# Mainboard.net
KiCad netlist of a schematic drawn in EAGLE
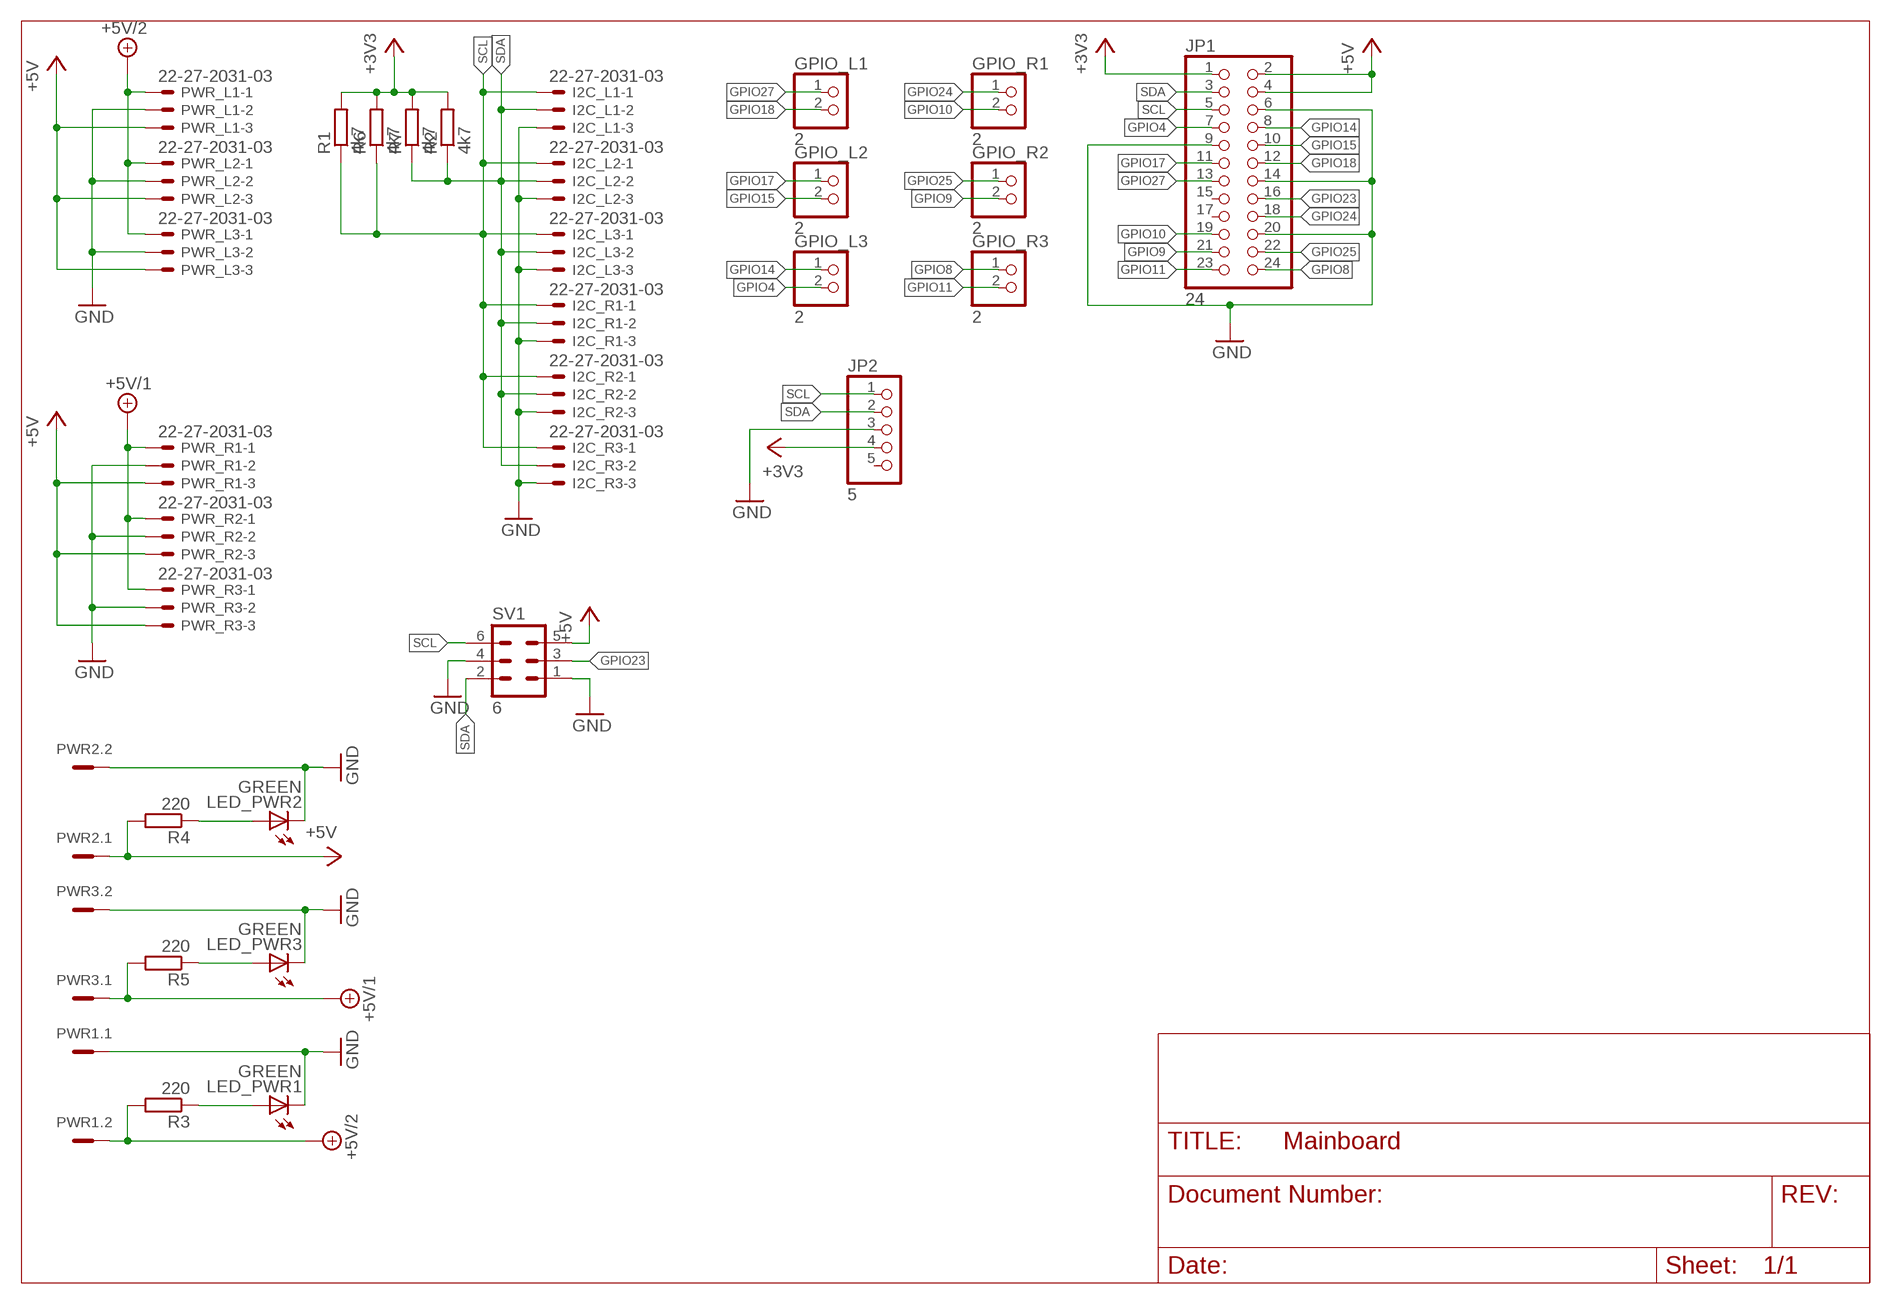
[diagram p0: schematic, sheet 1]

(export (version "E")
  (design (tool "Eeschema 10.0.6"))
  (components
    (comp (ref "GPIO_L1")
      (value "2")
      (footprint "eagle-import:1X02")
      (libsource (lib "eagle-import") (part "PINHD-1X2"))
    )
    (comp (ref "GPIO_L2")
      (value "2")
      (footprint "eagle-import:1X02")
      (libsource (lib "eagle-import") (part "PINHD-1X2"))
    )
    (comp (ref "GPIO_L3")
      (value "2")
      (footprint "eagle-import:1X02")
      (libsource (lib "eagle-import") (part "PINHD-1X2"))
    )
    (comp (ref "GPIO_R1")
      (value "2")
      (footprint "eagle-import:1X02")
      (libsource (lib "eagle-import") (part "PINHD-1X2"))
    )
    (comp (ref "GPIO_R2")
      (value "2")
      (footprint "eagle-import:1X02")
      (libsource (lib "eagle-import") (part "PINHD-1X2"))
    )
    (comp (ref "GPIO_R3")
      (value "2")
      (footprint "eagle-import:1X02")
      (libsource (lib "eagle-import") (part "PINHD-1X2"))
    )
    (comp (ref "I2C_L1")
      (value "22-27-2031-03")
      (footprint "eagle-import:6410-03")
      (libsource (lib "eagle-import") (part "22-?-0327-2031"))
    )
    (comp (ref "I2C_L2")
      (value "22-27-2031-03")
      (footprint "eagle-import:6410-03")
      (libsource (lib "eagle-import") (part "22-?-0327-2031"))
    )
    (comp (ref "I2C_L3")
      (value "22-27-2031-03")
      (footprint "eagle-import:6410-03")
      (libsource (lib "eagle-import") (part "22-?-0327-2031"))
    )
    (comp (ref "I2C_R1")
      (value "22-27-2031-03")
      (footprint "eagle-import:6410-03")
      (libsource (lib "eagle-import") (part "22-?-0327-2031"))
    )
    (comp (ref "I2C_R2")
      (value "22-27-2031-03")
      (footprint "eagle-import:6410-03")
      (libsource (lib "eagle-import") (part "22-?-0327-2031"))
    )
    (comp (ref "I2C_R3")
      (value "22-27-2031-03")
      (footprint "eagle-import:6410-03")
      (libsource (lib "eagle-import") (part "22-?-0327-2031"))
    )
    (comp (ref "JP1")
      (value "24")
      (footprint "eagle-import:2X12")
      (libsource (lib "eagle-import") (part "PINHD-2X12"))
    )
    (comp (ref "JP2")
      (value "5")
      (footprint "eagle-import:1X05")
      (libsource (lib "eagle-import") (part "PINHD-1X5"))
    )
    (comp (ref "LED_PWR1")
      (value "GREEN")
      (footprint "eagle-import:CHIP-LED0805")
      (libsource (lib "eagle-import") (part "LEDCHIP-LED0805"))
    )
    (comp (ref "LED_PWR2")
      (value "GREEN")
      (footprint "eagle-import:CHIP-LED0805")
      (libsource (lib "eagle-import") (part "LEDCHIP-LED0805"))
    )
    (comp (ref "LED_PWR3")
      (value "GREEN")
      (footprint "eagle-import:CHIP-LED0805")
      (libsource (lib "eagle-import") (part "LEDCHIP-LED0805"))
    )
    (comp (ref "PWR1")
      (value "MCV2")
      (footprint "eagle-import:MCV2")
      (libsource (lib "eagle-import") (part "MCV2"))
    )
    (comp (ref "PWR2")
      (value "MCV2")
      (footprint "eagle-import:MCV2")
      (libsource (lib "eagle-import") (part "MCV2"))
    )
    (comp (ref "PWR3")
      (value "MCV2")
      (footprint "eagle-import:MCV2")
      (libsource (lib "eagle-import") (part "MCV2"))
    )
    (comp (ref "PWR_L1")
      (value "22-27-2031-03")
      (footprint "eagle-import:6410-03")
      (libsource (lib "eagle-import") (part "22-?-0327-2031"))
    )
    (comp (ref "PWR_L2")
      (value "22-27-2031-03")
      (footprint "eagle-import:6410-03")
      (libsource (lib "eagle-import") (part "22-?-0327-2031"))
    )
    (comp (ref "PWR_L3")
      (value "22-27-2031-03")
      (footprint "eagle-import:6410-03")
      (libsource (lib "eagle-import") (part "22-?-0327-2031"))
    )
    (comp (ref "PWR_R1")
      (value "22-27-2031-03")
      (footprint "eagle-import:6410-03")
      (libsource (lib "eagle-import") (part "22-?-0327-2031"))
    )
    (comp (ref "PWR_R2")
      (value "22-27-2031-03")
      (footprint "eagle-import:6410-03")
      (libsource (lib "eagle-import") (part "22-?-0327-2031"))
    )
    (comp (ref "PWR_R3")
      (value "22-27-2031-03")
      (footprint "eagle-import:6410-03")
      (libsource (lib "eagle-import") (part "22-?-0327-2031"))
    )
    (comp (ref "R1")
      (value "4k7")
      (footprint "eagle-import:R0805")
      (libsource (lib "eagle-import") (part "R-EU_R0805"))
    )
    (comp (ref "R2")
      (value "4k7")
      (footprint "eagle-import:R0805")
      (libsource (lib "eagle-import") (part "R-EU_R0805"))
    )
    (comp (ref "R3")
      (value "220")
      (footprint "eagle-import:R0805")
      (libsource (lib "eagle-import") (part "R-EU_R0805"))
    )
    (comp (ref "R4")
      (value "220")
      (footprint "eagle-import:R0805")
      (libsource (lib "eagle-import") (part "R-EU_R0805"))
    )
    (comp (ref "R5")
      (value "220")
      (footprint "eagle-import:R0805")
      (libsource (lib "eagle-import") (part "R-EU_R0805"))
    )
    (comp (ref "R6")
      (value "4k7")
      (footprint "eagle-import:R0805")
      (libsource (lib "eagle-import") (part "R-EU_R0805"))
    )
    (comp (ref "R7")
      (value "4k7")
      (footprint "eagle-import:R0805")
      (libsource (lib "eagle-import") (part "R-EU_R0805"))
    )
    (comp (ref "SV1")
      (value "6")
      (footprint "eagle-import:ML6")
      (libsource (lib "eagle-import") (part "ML6"))
    )
  )
  (nets
    (net (code "1") (name "+3V3") (class "Default")
      (node (ref "JP1") (pin "1") (pinfunction "1_1") (pintype "passive"))
      (node (ref "JP2") (pin "4") (pinfunction "4_4") (pintype "passive"))
      (node (ref "R1") (pin "2") (pinfunction "2_2") (pintype "passive"))
      (node (ref "R2") (pin "2") (pinfunction "2_2") (pintype "passive"))
      (node (ref "R6") (pin "2") (pinfunction "2_2") (pintype "passive"))
      (node (ref "R7") (pin "2") (pinfunction "2_2") (pintype "passive"))
    )
    (net (code "2") (name "+5V") (class "Default")
      (node (ref "JP1") (pin "2") (pinfunction "2_2") (pintype "passive"))
      (node (ref "JP1") (pin "4") (pinfunction "4_4") (pintype "passive"))
      (node (ref "PWR2") (pin "1") (pinfunction "SK_1") (pintype "passive"))
      (node (ref "PWR_L1") (pin "3") (pinfunction "S_3") (pintype "passive"))
      (node (ref "PWR_L2") (pin "3") (pinfunction "S_3") (pintype "passive"))
      (node (ref "PWR_L3") (pin "3") (pinfunction "S_3") (pintype "passive"))
      (node (ref "PWR_R1") (pin "3") (pinfunction "S_3") (pintype "passive"))
      (node (ref "PWR_R2") (pin "3") (pinfunction "S_3") (pintype "passive"))
      (node (ref "PWR_R3") (pin "3") (pinfunction "S_3") (pintype "passive"))
      (node (ref "R4") (pin "2") (pinfunction "2_2") (pintype "passive"))
      (node (ref "SV1") (pin "5") (pinfunction "5_5") (pintype "passive"))
    )
    (net (code "3") (name "+5V{slash}1") (class "Default")
      (node (ref "PWR3") (pin "1") (pinfunction "SK_1") (pintype "passive"))
      (node (ref "PWR_R1") (pin "1") (pinfunction "S_1") (pintype "passive"))
      (node (ref "PWR_R2") (pin "1") (pinfunction "S_1") (pintype "passive"))
      (node (ref "PWR_R3") (pin "1") (pinfunction "S_1") (pintype "passive"))
      (node (ref "R5") (pin "2") (pinfunction "2_2") (pintype "passive"))
    )
    (net (code "4") (name "+5V{slash}2") (class "Default")
      (node (ref "PWR1") (pin "2") (pinfunction "SK_2") (pintype "passive"))
      (node (ref "PWR_L1") (pin "1") (pinfunction "S_1") (pintype "passive"))
      (node (ref "PWR_L2") (pin "1") (pinfunction "S_1") (pintype "passive"))
      (node (ref "PWR_L3") (pin "1") (pinfunction "S_1") (pintype "passive"))
      (node (ref "R3") (pin "2") (pinfunction "2_2") (pintype "passive"))
    )
    (net (code "5") (name "GND") (class "Default")
      (node (ref "I2C_L1") (pin "3") (pinfunction "S_3") (pintype "passive"))
      (node (ref "I2C_L2") (pin "3") (pinfunction "S_3") (pintype "passive"))
      (node (ref "I2C_L3") (pin "3") (pinfunction "S_3") (pintype "passive"))
      (node (ref "I2C_R1") (pin "3") (pinfunction "S_3") (pintype "passive"))
      (node (ref "I2C_R2") (pin "3") (pinfunction "S_3") (pintype "passive"))
      (node (ref "I2C_R3") (pin "3") (pinfunction "S_3") (pintype "passive"))
      (node (ref "JP1") (pin "14") (pinfunction "14_14") (pintype "passive"))
      (node (ref "JP1") (pin "20") (pinfunction "20_20") (pintype "passive"))
      (node (ref "JP1") (pin "6") (pinfunction "6_6") (pintype "passive"))
      (node (ref "JP1") (pin "9") (pinfunction "9_9") (pintype "passive"))
      (node (ref "JP2") (pin "3") (pinfunction "3_3") (pintype "passive"))
      (node (ref "LED_PWR1") (pin "C") (pinfunction "C_C") (pintype "passive"))
      (node (ref "LED_PWR2") (pin "C") (pinfunction "C_C") (pintype "passive"))
      (node (ref "LED_PWR3") (pin "C") (pinfunction "C_C") (pintype "passive"))
      (node (ref "PWR1") (pin "1") (pinfunction "SK_1") (pintype "passive"))
      (node (ref "PWR2") (pin "2") (pinfunction "SK_2") (pintype "passive"))
      (node (ref "PWR3") (pin "2") (pinfunction "SK_2") (pintype "passive"))
      (node (ref "PWR_L1") (pin "2") (pinfunction "S_2") (pintype "passive"))
      (node (ref "PWR_L2") (pin "2") (pinfunction "S_2") (pintype "passive"))
      (node (ref "PWR_L3") (pin "2") (pinfunction "S_2") (pintype "passive"))
      (node (ref "PWR_R1") (pin "2") (pinfunction "S_2") (pintype "passive"))
      (node (ref "PWR_R2") (pin "2") (pinfunction "S_2") (pintype "passive"))
      (node (ref "PWR_R3") (pin "2") (pinfunction "S_2") (pintype "passive"))
      (node (ref "SV1") (pin "1") (pinfunction "1_1") (pintype "passive"))
      (node (ref "SV1") (pin "4") (pinfunction "4_4") (pintype "passive"))
    )
    (net (code "6") (name "GPIO4") (class "Default")
      (node (ref "GPIO_L3") (pin "2") (pinfunction "2_2") (pintype "passive"))
      (node (ref "JP1") (pin "7") (pinfunction "7_7") (pintype "passive"))
    )
    (net (code "7") (name "GPIO8") (class "Default")
      (node (ref "GPIO_R3") (pin "1") (pinfunction "1_1") (pintype "passive"))
      (node (ref "JP1") (pin "24") (pinfunction "24_24") (pintype "passive"))
    )
    (net (code "8") (name "GPIO9") (class "Default")
      (node (ref "GPIO_R2") (pin "2") (pinfunction "2_2") (pintype "passive"))
      (node (ref "JP1") (pin "21") (pinfunction "21_21") (pintype "passive"))
    )
    (net (code "9") (name "GPIO10") (class "Default")
      (node (ref "GPIO_R1") (pin "2") (pinfunction "2_2") (pintype "passive"))
      (node (ref "JP1") (pin "19") (pinfunction "19_19") (pintype "passive"))
    )
    (net (code "10") (name "GPIO11") (class "Default")
      (node (ref "GPIO_R3") (pin "2") (pinfunction "2_2") (pintype "passive"))
      (node (ref "JP1") (pin "23") (pinfunction "23_23") (pintype "passive"))
    )
    (net (code "11") (name "GPIO14") (class "Default")
      (node (ref "GPIO_L3") (pin "1") (pinfunction "1_1") (pintype "passive"))
      (node (ref "JP1") (pin "8") (pinfunction "8_8") (pintype "passive"))
    )
    (net (code "12") (name "GPIO15") (class "Default")
      (node (ref "GPIO_L2") (pin "2") (pinfunction "2_2") (pintype "passive"))
      (node (ref "JP1") (pin "10") (pinfunction "10_10") (pintype "passive"))
    )
    (net (code "13") (name "GPIO17") (class "Default")
      (node (ref "GPIO_L2") (pin "1") (pinfunction "1_1") (pintype "passive"))
      (node (ref "JP1") (pin "11") (pinfunction "11_11") (pintype "passive"))
    )
    (net (code "14") (name "GPIO18") (class "Default")
      (node (ref "GPIO_L1") (pin "2") (pinfunction "2_2") (pintype "passive"))
      (node (ref "JP1") (pin "12") (pinfunction "12_12") (pintype "passive"))
    )
    (net (code "15") (name "GPIO23") (class "Default")
      (node (ref "JP1") (pin "16") (pinfunction "16_16") (pintype "passive"))
      (node (ref "SV1") (pin "3") (pinfunction "3_3") (pintype "passive"))
    )
    (net (code "16") (name "GPIO24") (class "Default")
      (node (ref "GPIO_R1") (pin "1") (pinfunction "1_1") (pintype "passive"))
      (node (ref "JP1") (pin "18") (pinfunction "18_18") (pintype "passive"))
    )
    (net (code "17") (name "GPIO25") (class "Default")
      (node (ref "GPIO_R2") (pin "1") (pinfunction "1_1") (pintype "passive"))
      (node (ref "JP1") (pin "22") (pinfunction "22_22") (pintype "passive"))
    )
    (net (code "18") (name "GPIO27") (class "Default")
      (node (ref "GPIO_L1") (pin "1") (pinfunction "1_1") (pintype "passive"))
      (node (ref "JP1") (pin "13") (pinfunction "13_13") (pintype "passive"))
    )
    (net (code "19") (name "Net-(LED_PWR1-PadA)") (class "Default")
      (node (ref "LED_PWR1") (pin "A") (pinfunction "A_A") (pintype "passive"))
      (node (ref "R3") (pin "1") (pinfunction "1_1") (pintype "passive"))
    )
    (net (code "20") (name "Net-(LED_PWR2-PadA)") (class "Default")
      (node (ref "LED_PWR2") (pin "A") (pinfunction "A_A") (pintype "passive"))
      (node (ref "R4") (pin "1") (pinfunction "1_1") (pintype "passive"))
    )
    (net (code "21") (name "Net-(LED_PWR3-PadA)") (class "Default")
      (node (ref "LED_PWR3") (pin "A") (pinfunction "A_A") (pintype "passive"))
      (node (ref "R5") (pin "1") (pinfunction "1_1") (pintype "passive"))
    )
    (net (code "22") (name "SCL") (class "Default")
      (node (ref "I2C_L1") (pin "1") (pinfunction "S_1") (pintype "passive"))
      (node (ref "I2C_L2") (pin "1") (pinfunction "S_1") (pintype "passive"))
      (node (ref "I2C_L3") (pin "1") (pinfunction "S_1") (pintype "passive"))
      (node (ref "I2C_R1") (pin "1") (pinfunction "S_1") (pintype "passive"))
      (node (ref "I2C_R2") (pin "1") (pinfunction "S_1") (pintype "passive"))
      (node (ref "I2C_R3") (pin "1") (pinfunction "S_1") (pintype "passive"))
      (node (ref "JP1") (pin "5") (pinfunction "5_5") (pintype "passive"))
      (node (ref "JP2") (pin "1") (pinfunction "1_1") (pintype "passive"))
      (node (ref "R1") (pin "1") (pinfunction "1_1") (pintype "passive"))
      (node (ref "R6") (pin "1") (pinfunction "1_1") (pintype "passive"))
      (node (ref "SV1") (pin "6") (pinfunction "6_6") (pintype "passive"))
    )
    (net (code "23") (name "SDA") (class "Default")
      (node (ref "I2C_L1") (pin "2") (pinfunction "S_2") (pintype "passive"))
      (node (ref "I2C_L2") (pin "2") (pinfunction "S_2") (pintype "passive"))
      (node (ref "I2C_L3") (pin "2") (pinfunction "S_2") (pintype "passive"))
      (node (ref "I2C_R1") (pin "2") (pinfunction "S_2") (pintype "passive"))
      (node (ref "I2C_R2") (pin "2") (pinfunction "S_2") (pintype "passive"))
      (node (ref "I2C_R3") (pin "2") (pinfunction "S_2") (pintype "passive"))
      (node (ref "JP1") (pin "3") (pinfunction "3_3") (pintype "passive"))
      (node (ref "JP2") (pin "2") (pinfunction "2_2") (pintype "passive"))
      (node (ref "R2") (pin "1") (pinfunction "1_1") (pintype "passive"))
      (node (ref "R7") (pin "1") (pinfunction "1_1") (pintype "passive"))
      (node (ref "SV1") (pin "2") (pinfunction "2_2") (pintype "passive"))
    )
    (net (code "24") (name "unconnected-(JP1-Pad15)") (class "Default")
      (node (ref "JP1") (pin "15") (pinfunction "15_15") (pintype "passive"))
    )
    (net (code "25") (name "unconnected-(JP1-Pad17)") (class "Default")
      (node (ref "JP1") (pin "17") (pinfunction "17_17") (pintype "passive"))
    )
    (net (code "26") (name "unconnected-(JP2-Pad5)") (class "Default")
      (node (ref "JP2") (pin "5") (pinfunction "5_5") (pintype "passive"))
    )
  )
)
